# MotorDriver_Mikroe.net
KiCad netlist of a schematic drawn in Altium Designer
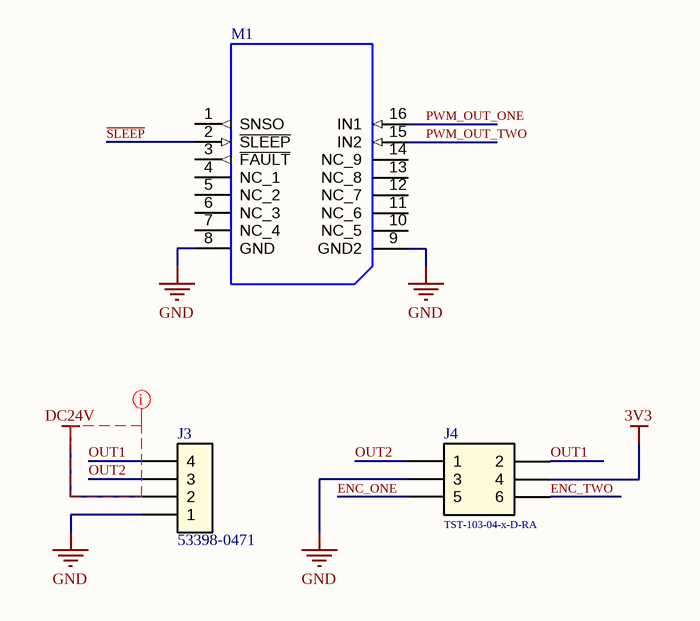
[diagram p0: MotorDriver.Mikroe.SchDoc]

(export (version "E")
  (design (tool "Eeschema 10.0.6"))
  (components
    (comp (ref "J3")
      (value "53398-0471")
      (footprint "FP-533980471-MFG")
      (libsource (lib "Sainsbury Wellcome Centre") (part "Jack 4x1"))
    )
    (comp (ref "J4")
      (value "TST-103-04-x-D-RA")
      (footprint "SAMTEC_TST-103-04-G-D-RA")
      (description "Board Connector, 6 Contact(s), 2 Row(s), Male, Right Angle, Solder Terminal")
      (fields (field (name "PARTNUMBER") "TST-103-04-G-D-RA"))
      (libsource (lib "Sainsbury Wellcome Centre") (part "Jack 3x2"))
    )
    (comp (ref "M1")
      (value "MIKROE-2699")
      (footprint "MIKROE-M")
      (description "DRV8701 Brushed DC Motor Full-Bridge Gate DC Motor Driver 5 Click Add-On Board")
      (libsource (lib "Sainsbury Wellcome Centre") (part "MIKROE-2699"))
    )
  )
  (nets
    (net (code "1") (name "/ENC_ONE") (class "Default")
      (node (ref "J4") (pin "5") (pinfunction "5_5") (pintype "passive"))
    )
    (net (code "2") (name "/ENC_TWO") (class "Default")
      (node (ref "J4") (pin "6") (pinfunction "6_6") (pintype "passive"))
    )
    (net (code "3") (name "/OUT1") (class "Default")
      (node (ref "J3") (pin "4") (pinfunction "4_4") (pintype "passive"))
      (node (ref "J4") (pin "2") (pinfunction "2_2") (pintype "passive"))
    )
    (net (code "4") (name "/OUT2") (class "Default")
      (node (ref "J3") (pin "3") (pinfunction "3_3") (pintype "passive"))
      (node (ref "J4") (pin "1") (pinfunction "1_1") (pintype "passive"))
    )
    (net (code "5") (name "/PWM_OUT_ONE") (class "Default")
      (node (ref "M1") (pin "16") (pinfunction "IN1_16") (pintype "input"))
    )
    (net (code "6") (name "/PWM_OUT_TWO") (class "Default")
      (node (ref "M1") (pin "15") (pinfunction "IN2_15") (pintype "input"))
    )
    (net (code "7") (name "/SLEEP") (class "Default")
      (node (ref "M1") (pin "2") (pinfunction "SLEEP_2") (pintype "input"))
    )
    (net (code "8") (name "3V3") (class "Default")
      (node (ref "J4") (pin "4") (pinfunction "4_4") (pintype "passive"))
    )
    (net (code "9") (name "DC24V") (class "Default")
      (node (ref "J3") (pin "2") (pinfunction "2_2") (pintype "passive"))
    )
    (net (code "10") (name "GND") (class "Default")
      (node (ref "J3") (pin "1") (pinfunction "1_1") (pintype "passive"))
      (node (ref "J4") (pin "3") (pinfunction "3_3") (pintype "passive"))
      (node (ref "M1") (pin "8") (pinfunction "GND_8") (pintype "power_in"))
      (node (ref "M1") (pin "9") (pinfunction "GND2_9") (pintype "power_in"))
    )
    (net (code "11") (name "unconnected-(M1-FAULT-Pad3)") (class "Default")
      (node (ref "M1") (pin "3") (pinfunction "FAULT_3") (pintype "output"))
    )
    (net (code "12") (name "unconnected-(M1-NC_1-Pad4)") (class "Default")
      (node (ref "M1") (pin "4") (pinfunction "NC_1_4") (pintype "passive"))
    )
    (net (code "13") (name "unconnected-(M1-NC_2-Pad5)") (class "Default")
      (node (ref "M1") (pin "5") (pinfunction "NC_2_5") (pintype "passive"))
    )
    (net (code "14") (name "unconnected-(M1-NC_3-Pad6)") (class "Default")
      (node (ref "M1") (pin "6") (pinfunction "NC_3_6") (pintype "passive"))
    )
    (net (code "15") (name "unconnected-(M1-NC_4-Pad7)") (class "Default")
      (node (ref "M1") (pin "7") (pinfunction "NC_4_7") (pintype "power_in"))
    )
    (net (code "16") (name "unconnected-(M1-NC_5-Pad10)") (class "Default")
      (node (ref "M1") (pin "10") (pinfunction "NC_5_10") (pintype "passive"))
    )
    (net (code "17") (name "unconnected-(M1-NC_6-Pad11)") (class "Default")
      (node (ref "M1") (pin "11") (pinfunction "NC_6_11") (pintype "passive"))
    )
    (net (code "18") (name "unconnected-(M1-NC_7-Pad12)") (class "Default")
      (node (ref "M1") (pin "12") (pinfunction "NC_7_12") (pintype "passive"))
    )
    (net (code "19") (name "unconnected-(M1-NC_8-Pad13)") (class "Default")
      (node (ref "M1") (pin "13") (pinfunction "NC_8_13") (pintype "passive"))
    )
    (net (code "20") (name "unconnected-(M1-NC_9-Pad14)") (class "Default")
      (node (ref "M1") (pin "14") (pinfunction "NC_9_14") (pintype "passive"))
    )
    (net (code "21") (name "unconnected-(M1-SNSO-Pad1)") (class "Default")
      (node (ref "M1") (pin "1") (pinfunction "SNSO_1") (pintype "output"))
    )
  )
)
